# Schematics.net
KiCad netlist of a schematic drawn in Altium Designer
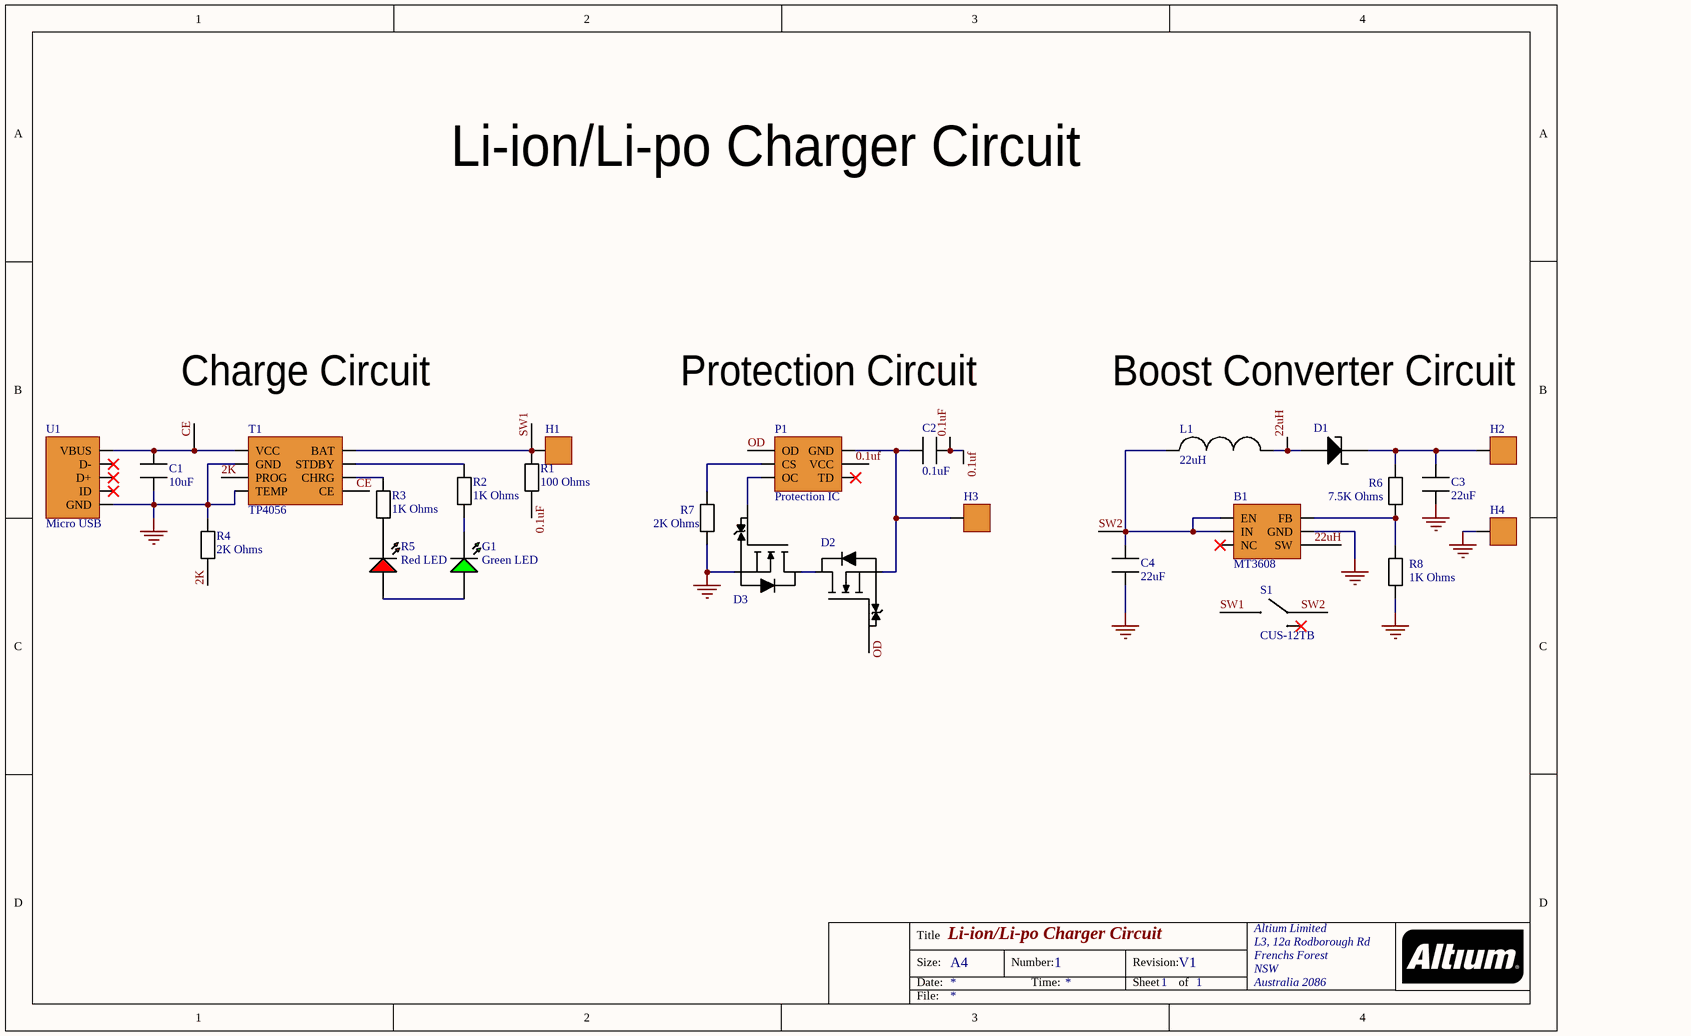
[diagram p0: Schematics.SchDoc]

(export (version "E")
  (design (tool "Eeschema 10.0.6"))
  (components
    (comp (ref "B1")
      (value "MT3608")
      (footprint "Boost Converter")
      (description "BOOST CONVERTER IC")
      (libsource (lib "Schematic Library") (part "MT3608"))
    )
    (comp (ref "C1")
      (value "10uF")
      (footprint "10uF Capacitor")
      (description "Cap Ceramic 10uF 6.3V Y5V -20% to 80% Pad SMD 0805 85C Automotive T/R")
      (fields
        (field (name "MANUFACTURER") "Yageo")
        (field (name "MANUFACTURER PART NUMBER") "CC0805ZKY5V5BB106")
      )
      (libsource (lib "Schematic Library") (part "CC0805ZKY5V5BB106"))
    )
    (comp (ref "C2")
      (value "0.1uF")
      (footprint "0.1uF Capacitor")
      (description "CAP CER 0.1UF 100V X7R 0805")
      (fields
        (field (name "MANUFACTURER") "Murata")
        (field (name "MANUFACTURER PART NUMBER") "GCM21BR72A104KA37L")
      )
      (libsource (lib "Schematic Library") (part "GCM21BR72A104KA37L"))
    )
    (comp (ref "C3")
      (value "22uF")
      (footprint "22uF Capacitor")
      (description "CAP CER 22UF 6.3V X6S 0603")
      (fields
        (field (name "MANUFACTURER") "Murata")
        (field (name "MANUFACTURER PART NUMBER") "GRM188C80J226ME15D")
      )
      (libsource (lib "Schematic Library") (part "GRM188C80J226ME15D"))
    )
    (comp (ref "C4")
      (value "22uF")
      (footprint "22uF Capacitor")
      (description "CAP CER 22UF 6.3V X6S 0603")
      (fields
        (field (name "MANUFACTURER") "Murata")
        (field (name "MANUFACTURER PART NUMBER") "GRM188C80J226ME15D")
      )
      (libsource (lib "Schematic Library") (part "GRM188C80J226ME15D"))
    )
    (comp (ref "D1")
      (value "Schottky Diode")
      (footprint "Diode")
      (description "Diode Schottky 40V 0.03A 2Pin SOD523")
      (fields (field (name "MANUFACTURER") "Diodes") (field (name "MANUFACTURER PART NUMBER") "SDM03U40-7"))
      (libsource (lib "Schematic Library") (part "SDM03U40-7"))
    )
    (comp (ref "D2")
      (value "N-Channel MOSFET")
      (footprint "MOSFET")
      (description "N-Channel Enhancement MOSFET SOT-23")
      (fields (field (name "MANUFACTURER") "Diodes") (field (name "MANUFACTURER PART NUMBER") "DMN65D8L-7"))
      (libsource (lib "Schematic Library") (part "DMN65D8L-7"))
    )
    (comp (ref "D3")
      (value "N-Channel MOSFET")
      (footprint "MOSFET")
      (description "N-Channel Enhancement MOSFET SOT-23")
      (fields (field (name "MANUFACTURER") "Diodes") (field (name "MANUFACTURER PART NUMBER") "DMN65D8L-7"))
      (libsource (lib "Schematic Library") (part "DMN65D8L-7"))
    )
    (comp (ref "G1")
      (value "Green LED")
      (footprint "Green LED")
      (description "SMD LED green 3.5 V 0805, 150080GS75000, Würth Elektronik")
      (fields
        (field (name "MANUFACTURER") "Wurth Electronics")
        (field (name "MANUFACTURER PART NUMBER") "150080GS75000")
      )
      (libsource (lib "Schematic Library") (part "150080GS75000"))
    )
    (comp (ref "H1")
      (value "1x1 Header")
      (footprint "Header 1x1")
      (description "CONN HEADER VERT 1POS")
      (fields
        (field (name "MANUFACTURER") "Wurth Electronics")
        (field (name "MANUFACTURER PART NUMBER") "61300111121")
      )
      (libsource (lib "Schematic Library") (part "61300111121"))
    )
    (comp (ref "H2")
      (value "1x1 Header")
      (footprint "Header 1x1")
      (description "CONN HEADER VERT 1POS")
      (fields
        (field (name "MANUFACTURER") "Wurth Electronics")
        (field (name "MANUFACTURER PART NUMBER") "61300111121")
      )
      (libsource (lib "Schematic Library") (part "61300111121"))
    )
    (comp (ref "H3")
      (value "1x1 Header")
      (footprint "Header 1x1")
      (description "CONN HEADER VERT 1POS")
      (fields
        (field (name "MANUFACTURER") "Wurth Electronics")
        (field (name "MANUFACTURER PART NUMBER") "61300111121")
      )
      (libsource (lib "Schematic Library") (part "61300111121"))
    )
    (comp (ref "H4")
      (value "1x1 Header")
      (footprint "Header 1x1")
      (description "CONN HEADER VERT 1POS")
      (fields
        (field (name "MANUFACTURER") "Wurth Electronics")
        (field (name "MANUFACTURER PART NUMBER") "61300111121")
      )
      (libsource (lib "Schematic Library") (part "61300111121"))
    )
    (comp (ref "L1")
      (value "22uH")
      (footprint "22uH Inductor")
      (description "Ind Power Shielded Wirewound 22uH 20% 100KHz Ferrite 3A T/R")
      (fields
        (field (name "MANUFACTURER") "Wurth Electronics")
        (field (name "MANUFACTURER PART NUMBER") "7447714220")
      )
      (libsource (lib "Schematic Library") (part "7447714220"))
    )
    (comp (ref "P1")
      (value "Protection IC")
      (footprint "Protection IC")
      (description "PROTECTION IC")
      (libsource (lib "Schematic Library") (part "FS312F-G"))
    )
    (comp (ref "R1")
      (value "100 Ohms")
      (footprint "100 Ohms")
      (description "RES SMD 100 OHM 1% 1/4W 0805")
      (fields
        (field (name "MANUFACTURER") "Stackpole Electronics")
        (field (name "MANUFACTURER PART NUMBER") "RNCP0805FTD100R")
      )
      (libsource (lib "Schematic Library") (part "RNCP0805FTD100R"))
    )
    (comp (ref "R2")
      (value "1K Ohms")
      (footprint "1K Resistor")
      (description "RES 1K OHM 1% 1/4W 0805")
      (fields
        (field (name "MANUFACTURER") "Stackpole Electronics")
        (field (name "MANUFACTURER PART NUMBER") "RNCP0805FTD1K00")
      )
      (libsource (lib "Schematic Library") (part "RNCP0805FTD1K00"))
    )
    (comp (ref "R3")
      (value "1K Ohms")
      (footprint "1K Resistor")
      (description "RES 1K OHM 1% 1/4W 0805")
      (fields
        (field (name "MANUFACTURER") "Stackpole Electronics")
        (field (name "MANUFACTURER PART NUMBER") "RNCP0805FTD1K00")
      )
      (libsource (lib "Schematic Library") (part "RNCP0805FTD1K00"))
    )
    (comp (ref "R4")
      (value "2K Ohms")
      (footprint "2K Resistor")
      (description "RES SMD 2K OHM 0.01% 1/8W 0805")
      (fields
        (field (name "MANUFACTURER") "Stackpole Electronics")
        (field (name "MANUFACTURER PART NUMBER") "RNCF0805TKY2K00")
      )
      (libsource (lib "Schematic Library") (part "RNCF0805TKY2K00"))
    )
    (comp (ref "R5")
      (value "Red LED")
      (footprint "Red LED")
      (description "SMD LED red 2.4 V 0805, 150080RS75000, Würth Elektronik")
      (fields
        (field (name "MANUFACTURER") "Wurth Electronics")
        (field (name "MANUFACTURER PART NUMBER") "150080RS75000")
      )
      (libsource (lib "Schematic Library") (part "150080RS75000"))
    )
    (comp (ref "R6")
      (value "7.5K Ohms")
      (footprint "7.5K Resistor")
      (description "RES SMD 7.5K OHM 1% 1/4W 0805")
      (fields
        (field (name "MANUFACTURER") "Stackpole Electronics")
        (field (name "MANUFACTURER PART NUMBER") "RNCP0805FTD7K50")
      )
      (libsource (lib "Schematic Library") (part "RNCP0805FTD7K50"))
    )
    (comp (ref "R7")
      (value "2K Ohms")
      (footprint "2K Resistor")
      (description "RES SMD 2K OHM 0.01% 1/8W 0805")
      (fields
        (field (name "MANUFACTURER") "Stackpole Electronics")
        (field (name "MANUFACTURER PART NUMBER") "RNCF0805TKY2K00")
      )
      (libsource (lib "Schematic Library") (part "RNCF0805TKY2K00"))
    )
    (comp (ref "R8")
      (value "1K Ohms")
      (footprint "1K Resistor")
      (description "RES 1K OHM 1% 1/4W 0805")
      (fields
        (field (name "MANUFACTURER") "Stackpole Electronics")
        (field (name "MANUFACTURER PART NUMBER") "RNCP0805FTD1K00")
      )
      (libsource (lib "Schematic Library") (part "RNCP0805FTD1K00"))
    )
    (comp (ref "S1")
      (value "CUS-12TB")
      (footprint "Slide Switch")
      (description "SWITCH SLIDE SPDT 300MA 4V")
      (fields (field (name "MANUFACTURER") "Nidec Copal"))
      (libsource (lib "Schematic Library") (part "CUS-12TB"))
    )
    (comp (ref "T1")
      (value "TP4056")
      (footprint "TP4056")
      (description "Li-ION/LI-PO CHARGE IC")
      (libsource (lib "Schematic Library") (part "TP4056"))
    )
    (comp (ref "U1")
      (value "Micro USB")
      (footprint "Micro USB")
      (fields
        (field (name "MANUFACTURER") "Wurth Electronics")
        (field (name "MANUFACTURER PART NUMBER") "629105136821")
      )
      (libsource (lib "Schematic Library") (part "629105136821"))
    )
  )
  (nets
    (net (code "1") (name "/0.1uF") (class "Default")
      (node (ref "C2") (pin "2") (pinfunction "2_2") (pintype "passive"))
      (node (ref "P1") (pin "5") (pinfunction "VCC_5") (pintype "passive"))
      (node (ref "R1") (pin "1") (pinfunction "1_1") (pintype "passive"))
    )
    (net (code "2") (name "/2K") (class "Default")
      (node (ref "R4") (pin "2") (pinfunction "2_2") (pintype "passive"))
      (node (ref "T1") (pin "2") (pinfunction "PROG_2") (pintype "passive"))
    )
    (net (code "3") (name "/22uH") (class "Default")
      (node (ref "B1") (pin "1") (pinfunction "SW_1") (pintype "passive"))
      (node (ref "D1") (pin "2") (pinfunction "2_2") (pintype "passive"))
      (node (ref "L1") (pin "2") (pinfunction "2_2") (pintype "passive"))
    )
    (net (code "4") (name "/CE") (class "Default")
      (node (ref "C1") (pin "2") (pinfunction "2_2") (pintype "passive"))
      (node (ref "T1") (pin "4") (pinfunction "VCC_4") (pintype "passive"))
      (node (ref "T1") (pin "8") (pinfunction "CE_8") (pintype "passive"))
      (node (ref "U1") (pin "1") (pinfunction "VBUS_1") (pintype "passive"))
    )
    (net (code "5") (name "/OD") (class "Default")
      (node (ref "D2") (pin "1") (pinfunction "G_1") (pintype "passive"))
      (node (ref "P1") (pin "1") (pinfunction "OD_1") (pintype "passive"))
    )
    (net (code "6") (name "/SW1") (class "Default")
      (node (ref "H1") (pin "1") (pinfunction "1_1") (pintype "passive"))
      (node (ref "R1") (pin "2") (pinfunction "2_2") (pintype "passive"))
      (node (ref "S1") (pin "1") (pinfunction "1_1") (pintype "passive"))
      (node (ref "T1") (pin "5") (pinfunction "BAT_5") (pintype "passive"))
    )
    (net (code "7") (name "/SW2") (class "Default")
      (node (ref "B1") (pin "4") (pinfunction "EN_4") (pintype "passive"))
      (node (ref "B1") (pin "5") (pinfunction "IN_5") (pintype "passive"))
      (node (ref "C4") (pin "2") (pinfunction "2_2") (pintype "passive"))
      (node (ref "L1") (pin "1") (pinfunction "1_1") (pintype "passive"))
      (node (ref "S1") (pin "2") (pinfunction "2_2") (pintype "passive"))
    )
    (net (code "8") (name "GND") (class "Default")
      (node (ref "B1") (pin "2") (pinfunction "GND_2") (pintype "passive"))
      (node (ref "C1") (pin "1") (pinfunction "1_1") (pintype "passive"))
      (node (ref "C3") (pin "1") (pinfunction "1_1") (pintype "passive"))
      (node (ref "C4") (pin "1") (pinfunction "1_1") (pintype "passive"))
      (node (ref "D3") (pin "3") (pinfunction "S_3") (pintype "passive"))
      (node (ref "H4") (pin "1") (pinfunction "1_1") (pintype "passive"))
      (node (ref "R4") (pin "1") (pinfunction "1_1") (pintype "passive"))
      (node (ref "R7") (pin "1") (pinfunction "1_1") (pintype "passive"))
      (node (ref "R8") (pin "1") (pinfunction "1_1") (pintype "passive"))
      (node (ref "T1") (pin "1") (pinfunction "TEMP_1") (pintype "passive"))
      (node (ref "T1") (pin "3") (pinfunction "GND_3") (pintype "passive"))
      (node (ref "U1") (pin "5") (pinfunction "GND_5") (pintype "passive"))
    )
    (net (code "9") (name "Net-(B1-FB)") (class "Default")
      (node (ref "B1") (pin "3") (pinfunction "FB_3") (pintype "passive"))
      (node (ref "R6") (pin "1") (pinfunction "1_1") (pintype "passive"))
      (node (ref "R8") (pin "2") (pinfunction "2_2") (pintype "passive"))
    )
    (net (code "10") (name "Net-(C3-Pad2)") (class "Default")
      (node (ref "C3") (pin "2") (pinfunction "2_2") (pintype "passive"))
      (node (ref "D1") (pin "1") (pinfunction "1_1") (pintype "passive"))
      (node (ref "H2") (pin "1") (pinfunction "1_1") (pintype "passive"))
      (node (ref "R6") (pin "2") (pinfunction "2_2") (pintype "passive"))
    )
    (net (code "11") (name "Net-(D2-D)") (class "Default")
      (node (ref "D2") (pin "2") (pinfunction "D_2") (pintype "passive"))
      (node (ref "D3") (pin "2") (pinfunction "D_2") (pintype "passive"))
    )
    (net (code "12") (name "Net-(D2-S)") (class "Default")
      (node (ref "C2") (pin "1") (pinfunction "1_1") (pintype "passive"))
      (node (ref "D2") (pin "3") (pinfunction "S_3") (pintype "passive"))
      (node (ref "H3") (pin "1") (pinfunction "1_1") (pintype "passive"))
      (node (ref "P1") (pin "6") (pinfunction "GND_6") (pintype "passive"))
    )
    (net (code "13") (name "Net-(D3-G)") (class "Default")
      (node (ref "D3") (pin "1") (pinfunction "G_1") (pintype "passive"))
      (node (ref "P1") (pin "3") (pinfunction "OC_3") (pintype "passive"))
    )
    (net (code "14") (name "Net-(G1-Pad1)") (class "Default")
      (node (ref "G1") (pin "1") (pinfunction "1_1") (pintype "passive"))
      (node (ref "R2") (pin "1") (pinfunction "1_1") (pintype "passive"))
    )
    (net (code "15") (name "Net-(G1-Pad2)") (class "Default")
      (node (ref "G1") (pin "2") (pinfunction "2_2") (pintype "passive"))
      (node (ref "R5") (pin "2") (pinfunction "2_2") (pintype "passive"))
    )
    (net (code "16") (name "Net-(P1-CS)") (class "Default")
      (node (ref "P1") (pin "2") (pinfunction "CS_2") (pintype "passive"))
      (node (ref "R7") (pin "2") (pinfunction "2_2") (pintype "passive"))
    )
    (net (code "17") (name "Net-(R3-Pad1)") (class "Default")
      (node (ref "R3") (pin "1") (pinfunction "1_1") (pintype "passive"))
      (node (ref "R5") (pin "1") (pinfunction "1_1") (pintype "passive"))
    )
    (net (code "18") (name "Net-(T1-CHRG)") (class "Default")
      (node (ref "R3") (pin "2") (pinfunction "2_2") (pintype "passive"))
      (node (ref "T1") (pin "7") (pinfunction "CHRG_7") (pintype "passive"))
    )
    (net (code "19") (name "Net-(T1-STDBY)") (class "Default")
      (node (ref "R2") (pin "2") (pinfunction "2_2") (pintype "passive"))
      (node (ref "T1") (pin "6") (pinfunction "STDBY_6") (pintype "passive"))
    )
    (net (code "20") (name "unconnected-(B1-NC-Pad6)") (class "Default")
      (node (ref "B1") (pin "6") (pinfunction "NC_6") (pintype "passive+no_connect"))
    )
    (net (code "21") (name "unconnected-(P1-TD-Pad4)") (class "Default")
      (node (ref "P1") (pin "4") (pinfunction "TD_4") (pintype "passive+no_connect"))
    )
    (net (code "22") (name "unconnected-(S1-Pad3)") (class "Default")
      (node (ref "S1") (pin "3") (pinfunction "3_3") (pintype "passive+no_connect"))
    )
    (net (code "23") (name "unconnected-(U1-D+-Pad3)") (class "Default")
      (node (ref "U1") (pin "3") (pinfunction "D+_3") (pintype "passive+no_connect"))
    )
    (net (code "24") (name "unconnected-(U1-D--Pad2)") (class "Default")
      (node (ref "U1") (pin "2") (pinfunction "D-_2") (pintype "passive+no_connect"))
    )
    (net (code "25") (name "unconnected-(U1-ID-Pad4)") (class "Default")
      (node (ref "U1") (pin "4") (pinfunction "ID_4") (pintype "passive+no_connect"))
    )
  )
)
